# ui_main_board.net
KiCad netlist of a schematic drawn in Altium Designer
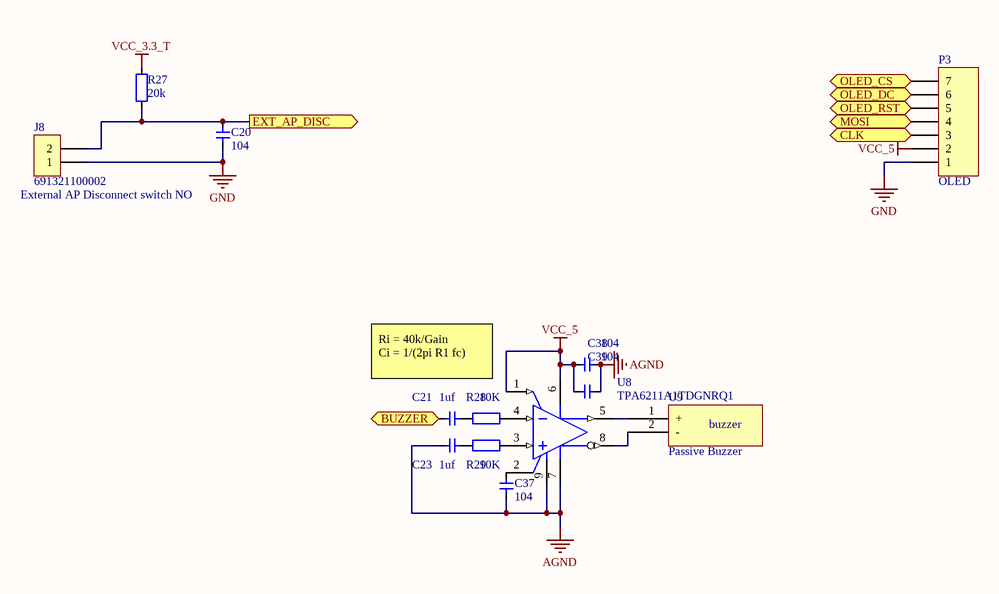
[diagram p0: ui_main_board.SchDoc]

(export (version "E")
  (design (tool "Eeschema 10.0.6"))
  (components
    (comp (ref "C20")
      (value "104")
      (footprint "PCB_PassiveCap:CAP_0603")
      (description "Capacitor")
      (fields (field (name "Comment") "Cap_0603"))
      (libsource (lib "SCH_Passive") (part "Cap_0603"))
    )
    (comp (ref "C21")
      (value "1uf")
      (footprint "PCB_PassiveCap:CAP_0603")
      (description "Capacitor")
      (fields (field (name "Comment") "Cap_0603"))
      (libsource (lib "SCH_Passive") (part "Cap_0603"))
    )
    (comp (ref "C23")
      (value "1uf")
      (footprint "PCB_PassiveCap:CAP_0603")
      (description "Capacitor")
      (fields (field (name "Comment") "Cap_0603"))
      (libsource (lib "SCH_Passive") (part "Cap_0603"))
    )
    (comp (ref "C37")
      (value "104")
      (footprint "PCB_PassiveCap:CAP_0603")
      (description "Capacitor")
      (fields (field (name "Comment") "Cap_0603"))
      (libsource (lib "SCH_Passive") (part "Cap_0603"))
    )
    (comp (ref "C38")
      (value "104")
      (footprint "PCB_PassiveCap:CAP_0603")
      (description "Capacitor")
      (fields (field (name "Comment") "Cap_0603"))
      (libsource (lib "SCH_Passive") (part "Cap_0603"))
    )
    (comp (ref "C39")
      (value "104")
      (footprint "PCB_PassiveCap:CAP_0603")
      (description "Capacitor")
      (fields (field (name "Comment") "Cap_0603"))
      (libsource (lib "SCH_Passive") (part "Cap_0603"))
    )
    (comp (ref "J8")
      (value "691321100002")
      (footprint "691322110002")
      (description "WR-TBL Terminal block - serie 3211 - 3.50 mm")
      (fields
        (field (name "MANUFACTURER") "Würth Elektronik eiSos GmbH")
        (field (name "CREATED BY") "Karrer Zheng")
      )
      (libsource (lib "ALTIUM-TBL_3_50_3211_VERTICAL_PCB_HEADER_69132110000X-rev15c") (part "691321100002"))
    )
    (comp (ref "P3")
      (value "OLED")
      (footprint "HDR1X7")
      (description "Header, 7-Pin")
      (fields (field (name "PUBLISHER") "Altium Limited"))
      (libsource (lib "Miscellaneous Connectors") (part "Header 7"))
    )
    (comp (ref "R27")
      (value "20k")
      (footprint "PCB_PassiveRes:RES_0603")
      (description "Resistor")
      (fields (field (name "Comment") "Res_0603"))
      (libsource (lib "SCH_Passive") (part "Res_0603"))
    )
    (comp (ref "R28")
      (value "10K")
      (footprint "PCB_PassiveRes:RES_0603")
      (description "Resistor")
      (fields (field (name "Comment") "Res_0603"))
      (libsource (lib "SCH_Passive") (part "Res_0603"))
    )
    (comp (ref "R29")
      (value "10K")
      (footprint "PCB_PassiveRes:RES_0603")
      (description "Resistor")
      (fields (field (name "Comment") "Res_0603"))
      (libsource (lib "SCH_Passive") (part "Res_0603"))
    )
    (comp (ref "U8")
      (value "TPA6211A1TDGNRQ1")
      (footprint "TI-DGN8-1760X1425TP_N")
      (fields (field (name "MANUFACTURER") "Texas Instruments"))
      (libsource (lib "TI Amplifiers and Linear Special Function Amplifier") (part "TPA6211A1TDGNRQ1"))
    )
    (comp (ref "U9")
      (value "Passive Buzzer")
      (footprint "62000211121")
      (libsource (lib "Schlib1") (part "Passive Buzzer"))
    )
  )
  (nets
    (net (code "1") (name "/BUZZER") (class "Default")
      (node (ref "C21") (pin "1") (pinfunction "1_1") (pintype "passive"))
    )
    (net (code "2") (name "/CLK") (class "Default")
      (node (ref "P3") (pin "3") (pinfunction "3_3") (pintype "passive"))
    )
    (net (code "3") (name "/EXT_AP_DISC") (class "Default")
      (node (ref "C20") (pin "2") (pinfunction "2_2") (pintype "passive"))
      (node (ref "J8") (pin "2") (pinfunction "2_2") (pintype "passive"))
      (node (ref "R27") (pin "1") (pinfunction "1_1") (pintype "passive"))
    )
    (net (code "4") (name "/MOSI") (class "Default")
      (node (ref "P3") (pin "4") (pinfunction "4_4") (pintype "passive"))
    )
    (net (code "5") (name "/OLED_CS") (class "Default")
      (node (ref "P3") (pin "7") (pinfunction "7_7") (pintype "passive"))
    )
    (net (code "6") (name "/OLED_DC") (class "Default")
      (node (ref "P3") (pin "6") (pinfunction "6_6") (pintype "passive"))
    )
    (net (code "7") (name "/OLED_RST") (class "Default")
      (node (ref "P3") (pin "5") (pinfunction "5_5") (pintype "passive"))
    )
    (net (code "8") (name "AGND") (class "Default")
      (node (ref "C23") (pin "1") (pinfunction "1_1") (pintype "passive"))
      (node (ref "C37") (pin "2") (pinfunction "2_2") (pintype "passive"))
      (node (ref "C38") (pin "2") (pinfunction "2_2") (pintype "passive"))
      (node (ref "C39") (pin "2") (pinfunction "2_2") (pintype "passive"))
      (node (ref "U8") (pin "7") (pinfunction "GND_7") (pintype "power_in"))
      (node (ref "U8") (pin "9") (pinfunction "EP_9") (pintype "power_in"))
    )
    (net (code "9") (name "GND") (class "Default")
      (node (ref "C20") (pin "1") (pinfunction "1_1") (pintype "passive"))
      (node (ref "J8") (pin "1") (pinfunction "1_1") (pintype "passive"))
      (node (ref "P3") (pin "1") (pinfunction "1_1") (pintype "passive"))
    )
    (net (code "10") (name "Net-(C21-Pad2)") (class "Default")
      (node (ref "C21") (pin "2") (pinfunction "2_2") (pintype "passive"))
      (node (ref "R28") (pin "1") (pinfunction "1_1") (pintype "passive"))
    )
    (net (code "11") (name "Net-(C23-Pad2)") (class "Default")
      (node (ref "C23") (pin "2") (pinfunction "2_2") (pintype "passive"))
      (node (ref "R29") (pin "1") (pinfunction "1_1") (pintype "passive"))
    )
    (net (code "12") (name "Net-(U8-BYPASS)") (class "Default")
      (node (ref "C37") (pin "1") (pinfunction "1_1") (pintype "passive"))
      (node (ref "U8") (pin "2") (pinfunction "BYPASS_2") (pintype "passive"))
    )
    (net (code "13") (name "Net-(U8-IN+)") (class "Default")
      (node (ref "R29") (pin "2") (pinfunction "2_2") (pintype "passive"))
      (node (ref "U8") (pin "3") (pinfunction "IN+_3") (pintype "input"))
    )
    (net (code "14") (name "Net-(U8-IN-)") (class "Default")
      (node (ref "R28") (pin "2") (pinfunction "2_2") (pintype "passive"))
      (node (ref "U8") (pin "4") (pinfunction "IN-_4") (pintype "input"))
    )
    (net (code "15") (name "Net-(U8-VO+)") (class "Default")
      (node (ref "U8") (pin "5") (pinfunction "VO+_5") (pintype "output"))
      (node (ref "U9") (pin "1") (pinfunction "+_1") (pintype "passive"))
    )
    (net (code "16") (name "Net-(U8-VO-)") (class "Default")
      (node (ref "U8") (pin "8") (pinfunction "VO-_8") (pintype "output"))
      (node (ref "U9") (pin "2") (pinfunction "-_2") (pintype "passive"))
    )
    (net (code "17") (name "VCC_3.3_T") (class "Default")
      (node (ref "R27") (pin "2") (pinfunction "2_2") (pintype "passive"))
    )
    (net (code "18") (name "VCC_5") (class "Default")
      (node (ref "C38") (pin "1") (pinfunction "1_1") (pintype "passive"))
      (node (ref "C39") (pin "1") (pinfunction "1_1") (pintype "passive"))
      (node (ref "P3") (pin "2") (pinfunction "2_2") (pintype "passive"))
      (node (ref "U8") (pin "1") (pinfunction "~{SHUTDOWN}_1") (pintype "input"))
      (node (ref "U8") (pin "6") (pinfunction "VDD_6") (pintype "power_in"))
    )
  )
)
